# JacdacDevRgbEc30_117.net
KiCad netlist of a schematic drawn in Altium Designer
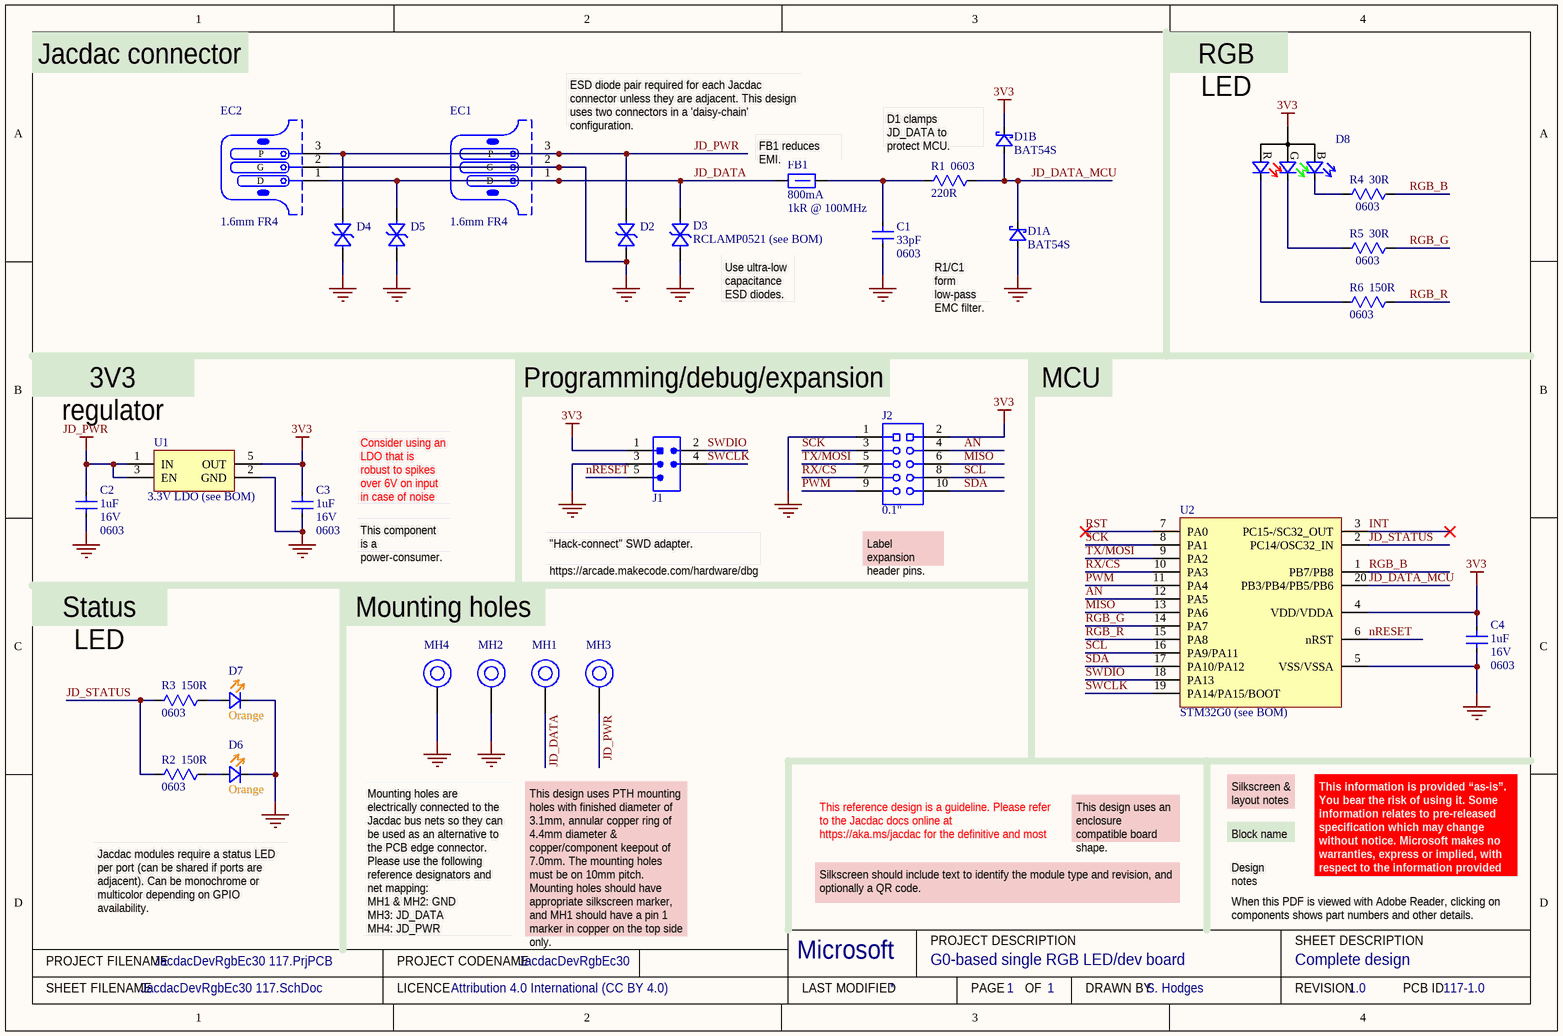
[diagram p0: JacdacDevRgbEc30 117.SchDoc]

(export (version "E")
  (design (tool "Eeschema 10.0.6"))
  (components
    (comp (ref "C1")
      (value "33pF")
      (footprint "YAGEO-0603:CC0603")
      (description "Cap 33PF 50V 0603 SMD 5% NP0")
      (fields
        (field (name "MANUFACTURER") "Yageo")
        (field (name "MANUFACTURER PART NUMBER") "CC0603JRNPO9BN330")
        (field (name "CAPACITANCE") "33pF")
        (field (name "CASE/PACKAGE") "0603")
      )
      (libsource (lib "Yageo") (part "CC0603JRNPO9BN330"))
    )
    (comp (ref "C2")
      (value "1uF 16V")
      (footprint "SAMSUNG-CAP-0603:C0603 - without outline")
      (description "SMD Multilayer Ceramic Capacitor, 1 µF, 16 V, 0603 [1608 Metric], ± 10%, X5R, CL Series")
      (fields
        (field (name "MANUFACTURER") "Samsung")
        (field (name "MANUFACTURER PART NUMBER") "CL10A105KO8NNNC")
        (field (name "VOLTAGE") "16V")
        (field (name "CASE/PACKAGE") "0603")
        (field (name "CAPACITANCE") "1uF")
      )
      (libsource (lib "Samsung") (part "CL10A105KO8NNNC"))
    )
    (comp (ref "C3")
      (value "1uF 16V")
      (footprint "SAMSUNG-CAP-0603:C0603 - without outline")
      (description "SMD Multilayer Ceramic Capacitor, 1 µF, 16 V, 0603 [1608 Metric], ± 10%, X5R, CL Series")
      (fields
        (field (name "MANUFACTURER") "Samsung")
        (field (name "MANUFACTURER PART NUMBER") "CL10A105KO8NNNC")
        (field (name "VOLTAGE") "16V")
        (field (name "CASE/PACKAGE") "0603")
        (field (name "CAPACITANCE") "1uF")
      )
      (libsource (lib "Samsung") (part "CL10A105KO8NNNC"))
    )
    (comp (ref "C4")
      (value "1uF 16V")
      (footprint "SAMSUNG-CAP-0603:C0603 - without outline")
      (description "SMD Multilayer Ceramic Capacitor, 1 µF, 16 V, 0603 [1608 Metric], ± 10%, X5R, CL Series")
      (fields
        (field (name "MANUFACTURER") "Samsung")
        (field (name "MANUFACTURER PART NUMBER") "CL10A105KO8NNNC")
        (field (name "VOLTAGE") "16V")
        (field (name "CASE/PACKAGE") "0603")
        (field (name "CAPACITANCE") "1uF")
      )
      (libsource (lib "Samsung") (part "CL10A105KO8NNNC"))
    )
    (comp (ref "D1")
      (value "BAT54S")
      (footprint "NXP-BAT54S-TO-236AB - without outline")
      (description "DIODE ARRAY SCHOTTKY 30V SOT23")
      (fields (field (name "MANUFACTURER") "Nexperia") (field (name "MANUFACTURER PART NUMBER") "BAT54S"))
      (libsource (lib "NXP") (part "BAT54S"))
    )
    (comp (ref "D2")
      (value "RCLAMP0521P-N")
      (footprint "0402:TVS 0402 - XL")
      (description "Bidirectional 5V (Max) 6V 16V 3.5A (8/20us) 0402 TVS RoHS")
      (fields
        (field (name "MANUFACTURER") "Born Semiconductor")
        (field (name "CREATED BY") "D Gakure")
        (field (name "CHECKED BY") "?")
      )
      (libsource (lib "BornSemiconductor") (part "RCLAMP0521P-N"))
    )
    (comp (ref "D3")
      (value "RCLAMP0521P-N")
      (footprint "0402:TVS 0402 - XL")
      (description "Bidirectional 5V (Max) 6V 16V 3.5A (8/20us) 0402 TVS RoHS")
      (fields
        (field (name "MANUFACTURER") "Born Semiconductor")
        (field (name "MANUFACTURER PART NUMBER") "RCLAMP0521 (see BOM)")
        (field (name "CREATED BY") "D Gakure")
        (field (name "CHECKED BY") "?")
      )
      (libsource (lib "BornSemiconductor") (part "RCLAMP0521P-N"))
    )
    (comp (ref "D4")
      (value "RCLAMP0521P-N")
      (footprint "0402:TVS 0402 - XL")
      (description "Bidirectional 5V (Max) 6V 16V 3.5A (8/20us) 0402 TVS RoHS")
      (fields
        (field (name "MANUFACTURER") "Born Semiconductor")
        (field (name "CREATED BY") "D Gakure")
        (field (name "CHECKED BY") "?")
      )
      (libsource (lib "BornSemiconductor") (part "RCLAMP0521P-N"))
    )
    (comp (ref "D5")
      (value "RCLAMP0521P-N")
      (footprint "0402:TVS 0402 - XL")
      (description "Bidirectional 5V (Max) 6V 16V 3.5A (8/20us) 0402 TVS RoHS")
      (fields
        (field (name "MANUFACTURER") "Born Semiconductor")
        (field (name "CREATED BY") "D Gakure")
        (field (name "CHECKED BY") "?")
      )
      (libsource (lib "BornSemiconductor") (part "RCLAMP0521P-N"))
    )
    (comp (ref "D6")
      (value "~")
      (footprint "0603 Orange")
      (description "LED ORANGE DIFFUSED 0603 SMD")
      (fields
        (field (name "MANUFACTURER") "Everlight Elec")
        (field (name "MANUFACTURER PART NUMBER") "19-217/S2C-AQ1R1B/3T")
        (field (name "COLOUR") "Orange")
      )
      (libsource (lib "EverlightElec") (part "19-217/S2C-AQ1R1B/3T"))
    )
    (comp (ref "D7")
      (value "~")
      (footprint "0603 Orange")
      (description "LED ORANGE DIFFUSED 0603 SMD")
      (fields
        (field (name "MANUFACTURER") "Everlight Elec")
        (field (name "MANUFACTURER PART NUMBER") "19-217/S2C-AQ1R1B/3T")
        (field (name "COLOUR") "Orange")
      )
      (libsource (lib "EverlightElec") (part "19-217/S2C-AQ1R1B/3T"))
    )
    (comp (ref "D8")
      (value "TZ-P4-1615RGBTCA1-0.55T")
      (footprint "TZ-P4-1615RGBTCA1-0.55T")
      (description "1615 Light Emitting Diodes (LED) RoHS")
      (fields
        (field (name "MANUFACTURER") "TUOZHAN")
        (field (name "CREATED BY") "D. Gakure")
        (field (name "CHECKED BY") "?")
      )
      (libsource (lib "Tuozhan") (part "TZ-P4-1615RGBTCA1-0.55T"))
    )
    (comp (ref "EC1")
      (value "3 pin JACDAC edge connector")
      (footprint "JACDAC_edge_connector:JACDAC_EDGE_CONNECTOR_NO_TRACES")
      (description "3 pin Jacdac edge connector 1.27mm pitch")
      (fields
        (field (name "MANUFACTURER PART NUMBER") "JACDAC_EDGE_CONNECTOR")
        (field (name "PCB TYPE") "1.6mm FR4")
        (field (name "CHECKED BY") "?")
        (field (name "CREATED BY") "D. Gakure")
      )
      (libsource (lib "generic-con") (part "Jacdac edge connector"))
    )
    (comp (ref "EC2")
      (value "3 pin JACDAC edge connector")
      (footprint "JACDAC_edge_connector:JACDAC_EDGE_CONNECTOR_NO_TRACES")
      (description "3 pin Jacdac edge connector 1.27mm pitch")
      (fields
        (field (name "MANUFACTURER PART NUMBER") "JACDAC_EDGE_CONNECTOR")
        (field (name "PCB TYPE") "1.6mm FR4")
        (field (name "CHECKED BY") "?")
        (field (name "CREATED BY") "D. Gakure")
      )
      (libsource (lib "generic-con") (part "Jacdac edge connector"))
    )
    (comp (ref "FB1")
      (value "TDK MPZ1608S102ATA00")
      (footprint "TDK MPZ1608 0.8mm - without outline")
      (description "0603 1k@100MHz 0.8A chip")
      (fields
        (field (name "TOLERANCE") "25%")
        (field (name "MANUFACTURER") "TDK")
        (field (name "CURRENT RATING") "800mA")
        (field (name "IMPEDANCE") "1kR @ 100MHz")
      )
      (libsource (lib "TDK") (part "TDK MPZ1608S102ATA00"))
    )
    (comp (ref "J1")
      (value "Hack Connect Mini 1.27 mm pitch 2-row")
      (footprint "HACK_CONNECT_MINI_5_X_1_27")
      (libsource (lib "HackConnect") (part "HACK_CONNECT_MINI"))
    )
    (comp (ref "J2")
      (value "0.1\"")
      (footprint "generic-con-0.1inch:Generic 2x5 2.54mm header")
      (description "2.54mm, 5x2 way, vertical, square pin, gold plate")
      (fields (field (name "MANUFACTURER") "Multicomp") (field (name "MANUFACTURER PART NUMBER") "2213S-10G"))
      (libsource (lib "generic-con") (part "Header Multicomp 2213S-10G-whitesch"))
    )
    (comp (ref "MH1")
      (value "MH_7.0MMK_4.4MMC_3.1MMD_PTH")
      (footprint "MH_7.0MMK_4.4MMC_3.1MMD_PTH:MH_7.0MMK_4.4MMC_3.1MMD_PTH")
      (description "Mounting Hole 7.0mm keepout, 4.4mm annualar ring and 3.1mm Drill PTH")
      (libsource (lib "generic") (part "MH_7.0MMK_4.4MMC_3.1MMD_PTH"))
    )
    (comp (ref "MH2")
      (value "MH_7.0MMK_4.4MMC_3.1MMD_PTH")
      (footprint "MH_7.0MMK_4.4MMC_3.1MMD_PTH:MH_7.0MMK_4.4MMC_3.1MMD_PTH")
      (description "Mounting Hole 7.0mm keepout, 4.4mm annualar ring and 3.1mm Drill PTH")
      (libsource (lib "generic") (part "MH_7.0MMK_4.4MMC_3.1MMD_PTH"))
    )
    (comp (ref "MH3")
      (value "MH_7.0MMK_4.4MMC_3.1MMD_PTH")
      (footprint "MH_7.0MMK_4.4MMC_3.1MMD_PTH:MH_7.0MMK_4.4MMC_3.1MMD_PTH")
      (description "Mounting Hole 7.0mm keepout, 4.4mm annualar ring and 3.1mm Drill PTH")
      (libsource (lib "generic") (part "MH_7.0MMK_4.4MMC_3.1MMD_PTH"))
    )
    (comp (ref "MH4")
      (value "MH_7.0MMK_4.4MMC_3.1MMD_PTH")
      (footprint "MH_7.0MMK_4.4MMC_3.1MMD_PTH:MH_7.0MMK_4.4MMC_3.1MMD_PTH")
      (description "Mounting Hole 7.0mm keepout, 4.4mm annualar ring and 3.1mm Drill PTH")
      (libsource (lib "generic") (part "MH_7.0MMK_4.4MMC_3.1MMD_PTH"))
    )
    (comp (ref "R1")
      (value "220R")
      (footprint "YAGEO-0603:RC0603")
      (description "Res Thick Film 0603 220 Ohm 1% 0.1W(1/10W) ±100ppm/°C Pad SMD T/R")
      (fields
        (field (name "MANUFACTURER") "Yageo")
        (field (name "MANUFACTURER PART NUMBER") "RC0603FR-07220RL")
        (field (name "RESISTANCE") "220R")
        (field (name "CASE/PACKAGE") "0603")
      )
      (libsource (lib "Yageo") (part "RC0603FR-07220RL"))
    )
    (comp (ref "R2")
      (value "150R")
      (footprint "YAGEO-0603:RC0603")
      (description "Res General Purpose Thick Film 0603 150 Ohm 1% 1/10W ±100ppm/°C Molded SMD Paper T/R")
      (fields
        (field (name "MANUFACTURER") "Yageo")
        (field (name "MANUFACTURER PART NUMBER") "RC0603FR-07150RL")
        (field (name "CASE/PACKAGE") "0603")
        (field (name "RESISTANCE") "150R")
      )
      (libsource (lib "Yageo") (part "RC0603FR-07150RL"))
    )
    (comp (ref "R3")
      (value "150R")
      (footprint "YAGEO-0603:RC0603")
      (description "Res General Purpose Thick Film 0603 150 Ohm 1% 1/10W ±100ppm/°C Molded SMD Paper T/R")
      (fields
        (field (name "MANUFACTURER") "Yageo")
        (field (name "MANUFACTURER PART NUMBER") "RC0603FR-07150RL")
        (field (name "CASE/PACKAGE") "0603")
        (field (name "RESISTANCE") "150R")
      )
      (libsource (lib "Yageo") (part "RC0603FR-07150RL"))
    )
    (comp (ref "R4")
      (value "30R")
      (footprint "YAGEO-0603:RC0603")
      (description "Res Thick Film 0603 30 Ohm 1% 0.1W(1/10W) ±100ppm/C Pad SMD T/R")
      (fields
        (field (name "MANUFACTURER") "Yageo")
        (field (name "MANUFACTURER PART NUMBER") "RC0603FR-0730RL")
        (field (name "RESISTANCE") "30R")
        (field (name "CASE/PACKAGE") "0603")
      )
      (libsource (lib "Yageo") (part "RC0603FR-0730RL"))
    )
    (comp (ref "R5")
      (value "30R")
      (footprint "YAGEO-0603:RC0603")
      (description "Res Thick Film 0603 30 Ohm 1% 0.1W(1/10W) ±100ppm/C Pad SMD T/R")
      (fields
        (field (name "MANUFACTURER") "Yageo")
        (field (name "MANUFACTURER PART NUMBER") "RC0603FR-0730RL")
        (field (name "RESISTANCE") "30R")
        (field (name "CASE/PACKAGE") "0603")
      )
      (libsource (lib "Yageo") (part "RC0603FR-0730RL"))
    )
    (comp (ref "R6")
      (value "150R")
      (footprint "YAGEO-0603:RC0603")
      (description "Res General Purpose Thick Film 0603 150 Ohm 1% 1/10W ±100ppm/°C Molded SMD Paper T/R")
      (fields
        (field (name "MANUFACTURER") "Yageo")
        (field (name "MANUFACTURER PART NUMBER") "RC0603FR-07150RL")
        (field (name "CASE/PACKAGE") "0603")
        (field (name "RESISTANCE") "150R")
      )
      (libsource (lib "Yageo") (part "RC0603FR-07150RL"))
    )
    (comp (ref "U1")
      (value "3.3V LDO (see BOM)")
      (footprint "MICRONE-SOT23-5")
      (description "6V 260mV @ 200mA(typ) - - Fixed 3.3V SOT-23-5 Linear Voltage Regulators (LDO) ROHS")
      (fields
        (field (name "MANUFACTURER") "MICRONE(Nanjing Micro One Elec)")
        (field (name "MANUFACTURER PART NUMBER") "ME6211C33M5G-N")
        (field (name "CREATED") "DG")
        (field (name "CHECKED") "?")
      )
      (libsource (lib "MICRONE(NanjingMicroOneElec)") (part "ME6211C33M5G-N"))
    )
    (comp (ref "U2")
      (value "STM32G0 (see BOM)")
      (footprint "20-TSSOP")
      (description "MCU 32-Bit STM32G031 ARM Cortex-M0+ RISC 32KB Flash 1.7V to 3.6V 20-Pin TSSOP Tube")
      (fields
        (field (name "MANUFACTURER") "STMicroelectronics")
        (field (name "MANUFACTURER PART NUMBER") "STM32G031F6P6")
        (field (name "CREATED BY") "D. Gakure")
        (field (name "CHECKED BY") "?")
      )
      (libsource (lib "ST") (part "STM32G031F6P6"))
    )
  )
  (nets
    (net (code "1") (name "/AN") (class "Default")
      (node (ref "J2") (pin "4") (pinfunction "4_4") (pintype "passive"))
      (node (ref "U2") (pin "12") (pinfunction "PA5_12") (pintype "passive"))
    )
    (net (code "2") (name "/INT") (class "Default")
      (node (ref "U2") (pin "3") (pinfunction "PC15-/SC32_OUT_3") (pintype "passive+no_connect"))
    )
    (net (code "3") (name "/JD_DATA") (class "Default")
      (node (ref "D3") (pin "1") (pinfunction "K_1") (pintype "passive"))
      (node (ref "D5") (pin "1") (pinfunction "K_1") (pintype "passive"))
      (node (ref "EC1") (pin "1") (pinfunction "D_1") (pintype "passive"))
      (node (ref "EC2") (pin "1") (pinfunction "D_1") (pintype "passive"))
      (node (ref "FB1") (pin "1") (pinfunction "1_1") (pintype "passive"))
      (node (ref "MH1") (pin "1") (pinfunction "1_1") (pintype "passive"))
    )
    (net (code "4") (name "/JD_DATA_MCU") (class "Default")
      (node (ref "D1") (pin "3") (pinfunction "A_3") (pintype "passive"))
      (node (ref "R1") (pin "2") (pinfunction "2_2") (pintype "passive"))
      (node (ref "U2") (pin "20") (pinfunction "PB3/PB4/PB5/PB6_20") (pintype "power_in"))
    )
    (net (code "5") (name "/JD_STATUS") (class "Default")
      (node (ref "R2") (pin "1") (pinfunction "1_1") (pintype "passive"))
      (node (ref "R3") (pin "1") (pinfunction "1_1") (pintype "passive"))
      (node (ref "U2") (pin "2") (pinfunction "PC14/OSC32_IN_2") (pintype "passive"))
    )
    (net (code "6") (name "/MISO") (class "Default")
      (node (ref "J2") (pin "6") (pinfunction "6_6") (pintype "passive"))
      (node (ref "U2") (pin "13") (pinfunction "PA6_13") (pintype "passive"))
    )
    (net (code "7") (name "/PWM") (class "Default")
      (node (ref "J2") (pin "9") (pinfunction "9_9") (pintype "passive"))
      (node (ref "U2") (pin "11") (pinfunction "PA4_11") (pintype "passive"))
    )
    (net (code "8") (name "/RGB_B") (class "Default")
      (node (ref "R4") (pin "2") (pinfunction "2_2") (pintype "passive"))
      (node (ref "U2") (pin "1") (pinfunction "PB7/PB8_1") (pintype "passive"))
    )
    (net (code "9") (name "/RGB_G") (class "Default")
      (node (ref "R5") (pin "2") (pinfunction "2_2") (pintype "passive"))
      (node (ref "U2") (pin "14") (pinfunction "PA7_14") (pintype "passive"))
    )
    (net (code "10") (name "/RGB_R") (class "Default")
      (node (ref "R6") (pin "2") (pinfunction "2_2") (pintype "passive"))
      (node (ref "U2") (pin "15") (pinfunction "PA8_15") (pintype "passive"))
    )
    (net (code "11") (name "/RST") (class "Default")
      (node (ref "U2") (pin "7") (pinfunction "PA0_7") (pintype "passive+no_connect"))
    )
    (net (code "12") (name "/RX{slash}CS") (class "Default")
      (node (ref "J2") (pin "7") (pinfunction "7_7") (pintype "passive"))
      (node (ref "U2") (pin "10") (pinfunction "PA3_10") (pintype "passive"))
    )
    (net (code "13") (name "/SCK") (class "Default")
      (node (ref "J2") (pin "3") (pinfunction "3_3") (pintype "passive"))
      (node (ref "U2") (pin "8") (pinfunction "PA1_8") (pintype "passive"))
    )
    (net (code "14") (name "/SCL") (class "Default")
      (node (ref "J2") (pin "8") (pinfunction "8_8") (pintype "passive"))
      (node (ref "U2") (pin "16") (pinfunction "PA9/PA11_16") (pintype "passive"))
    )
    (net (code "15") (name "/SDA") (class "Default")
      (node (ref "J2") (pin "10") (pinfunction "10_10") (pintype "passive"))
      (node (ref "U2") (pin "17") (pinfunction "PA10/PA12_17") (pintype "passive"))
    )
    (net (code "16") (name "/SWCLK") (class "Default")
      (node (ref "J1") (pin "4") (pinfunction "SWCLK_4") (pintype "passive"))
      (node (ref "U2") (pin "19") (pinfunction "PA14/PA15/BOOT_19") (pintype "passive"))
    )
    (net (code "17") (name "/SWDIO") (class "Default")
      (node (ref "J1") (pin "2") (pinfunction "SWDIO_2") (pintype "passive"))
      (node (ref "U2") (pin "18") (pinfunction "PA13_18") (pintype "passive"))
    )
    (net (code "18") (name "/TX{slash}MOSI") (class "Default")
      (node (ref "J2") (pin "5") (pinfunction "5_5") (pintype "passive"))
      (node (ref "U2") (pin "9") (pinfunction "PA2_9") (pintype "passive"))
    )
    (net (code "19") (name "/nRESET") (class "Default")
      (node (ref "J1") (pin "5") (pinfunction "RESET_5") (pintype "passive"))
      (node (ref "U2") (pin "6") (pinfunction "nRST_6") (pintype "power_in"))
    )
    (net (code "20") (name "3V3") (class "Default")
      (node (ref "C3") (pin "2") (pinfunction "2_2") (pintype "passive"))
      (node (ref "C4") (pin "2") (pinfunction "2_2") (pintype "passive"))
      (node (ref "D1") (pin "2") (pinfunction "K_2") (pintype "passive"))
      (node (ref "D8") (pin "1") (pinfunction "A_1") (pintype "passive"))
      (node (ref "J1") (pin "1") (pinfunction "VCC_1") (pintype "passive"))
      (node (ref "J2") (pin "2") (pinfunction "2_2") (pintype "passive"))
      (node (ref "U1") (pin "5") (pinfunction "OUT_5") (pintype "passive"))
      (node (ref "U2") (pin "4") (pinfunction "VDD/VDDA_4") (pintype "passive"))
    )
    (net (code "21") (name "GND") (class "Default")
      (node (ref "C1") (pin "1") (pinfunction "1_1") (pintype "passive"))
      (node (ref "C2") (pin "1") (pinfunction "1_1") (pintype "passive"))
      (node (ref "C3") (pin "1") (pinfunction "1_1") (pintype "passive"))
      (node (ref "C4") (pin "1") (pinfunction "1_1") (pintype "passive"))
      (node (ref "D1") (pin "1") (pinfunction "A_1") (pintype "passive"))
      (node (ref "D2") (pin "2") (pinfunction "A_2") (pintype "passive"))
      (node (ref "D3") (pin "2") (pinfunction "A_2") (pintype "passive"))
      (node (ref "D4") (pin "2") (pinfunction "A_2") (pintype "passive"))
      (node (ref "D5") (pin "2") (pinfunction "A_2") (pintype "passive"))
      (node (ref "D6") (pin "1") (pinfunction "K_1") (pintype "passive"))
      (node (ref "D7") (pin "1") (pinfunction "K_1") (pintype "passive"))
      (node (ref "EC1") (pin "2") (pinfunction "G_2") (pintype "passive"))
      (node (ref "EC2") (pin "2") (pinfunction "G_2") (pintype "passive"))
      (node (ref "J1") (pin "3") (pinfunction "GND_3") (pintype "passive"))
      (node (ref "J2") (pin "1") (pinfunction "1_1") (pintype "passive"))
      (node (ref "MH2") (pin "1") (pinfunction "1_1") (pintype "passive"))
      (node (ref "MH4") (pin "1") (pinfunction "1_1") (pintype "passive"))
      (node (ref "U1") (pin "2") (pinfunction "GND_2") (pintype "passive"))
      (node (ref "U2") (pin "5") (pinfunction "VSS/VSSA_5") (pintype "power_in"))
    )
    (net (code "22") (name "JD_PWR") (class "Default")
      (node (ref "C2") (pin "2") (pinfunction "2_2") (pintype "passive"))
      (node (ref "D2") (pin "1") (pinfunction "K_1") (pintype "passive"))
      (node (ref "D4") (pin "1") (pinfunction "K_1") (pintype "passive"))
      (node (ref "EC1") (pin "3") (pinfunction "P_3") (pintype "passive"))
      (node (ref "EC2") (pin "3") (pinfunction "P_3") (pintype "passive"))
      (node (ref "MH3") (pin "1") (pinfunction "1_1") (pintype "passive"))
      (node (ref "U1") (pin "1") (pinfunction "IN_1") (pintype "passive"))
      (node (ref "U1") (pin "3") (pinfunction "EN_3") (pintype "passive"))
    )
    (net (code "23") (name "Net-(C1-Pad2)") (class "Default")
      (node (ref "C1") (pin "2") (pinfunction "2_2") (pintype "passive"))
      (node (ref "FB1") (pin "2") (pinfunction "2_2") (pintype "passive"))
      (node (ref "R1") (pin "1") (pinfunction "1_1") (pintype "passive"))
    )
    (net (code "24") (name "Net-(D6-A)") (class "Default")
      (node (ref "D6") (pin "2") (pinfunction "A_2") (pintype "passive"))
      (node (ref "R2") (pin "2") (pinfunction "2_2") (pintype "passive"))
    )
    (net (code "25") (name "Net-(D7-A)") (class "Default")
      (node (ref "D7") (pin "2") (pinfunction "A_2") (pintype "passive"))
      (node (ref "R3") (pin "2") (pinfunction "2_2") (pintype "passive"))
    )
    (net (code "26") (name "Net-(D8-B)") (class "Default")
      (node (ref "D8") (pin "4") (pinfunction "B_4") (pintype "passive"))
      (node (ref "R4") (pin "1") (pinfunction "1_1") (pintype "passive"))
    )
    (net (code "27") (name "Net-(D8-G)") (class "Default")
      (node (ref "D8") (pin "3") (pinfunction "G_3") (pintype "passive"))
      (node (ref "R5") (pin "1") (pinfunction "1_1") (pintype "passive"))
    )
    (net (code "28") (name "Net-(D8-R)") (class "Default")
      (node (ref "D8") (pin "2") (pinfunction "R_2") (pintype "passive"))
      (node (ref "R6") (pin "1") (pinfunction "1_1") (pintype "passive"))
    )
  )
)
